# Main_PCB.net
KiCad netlist of a schematic drawn in EAGLE
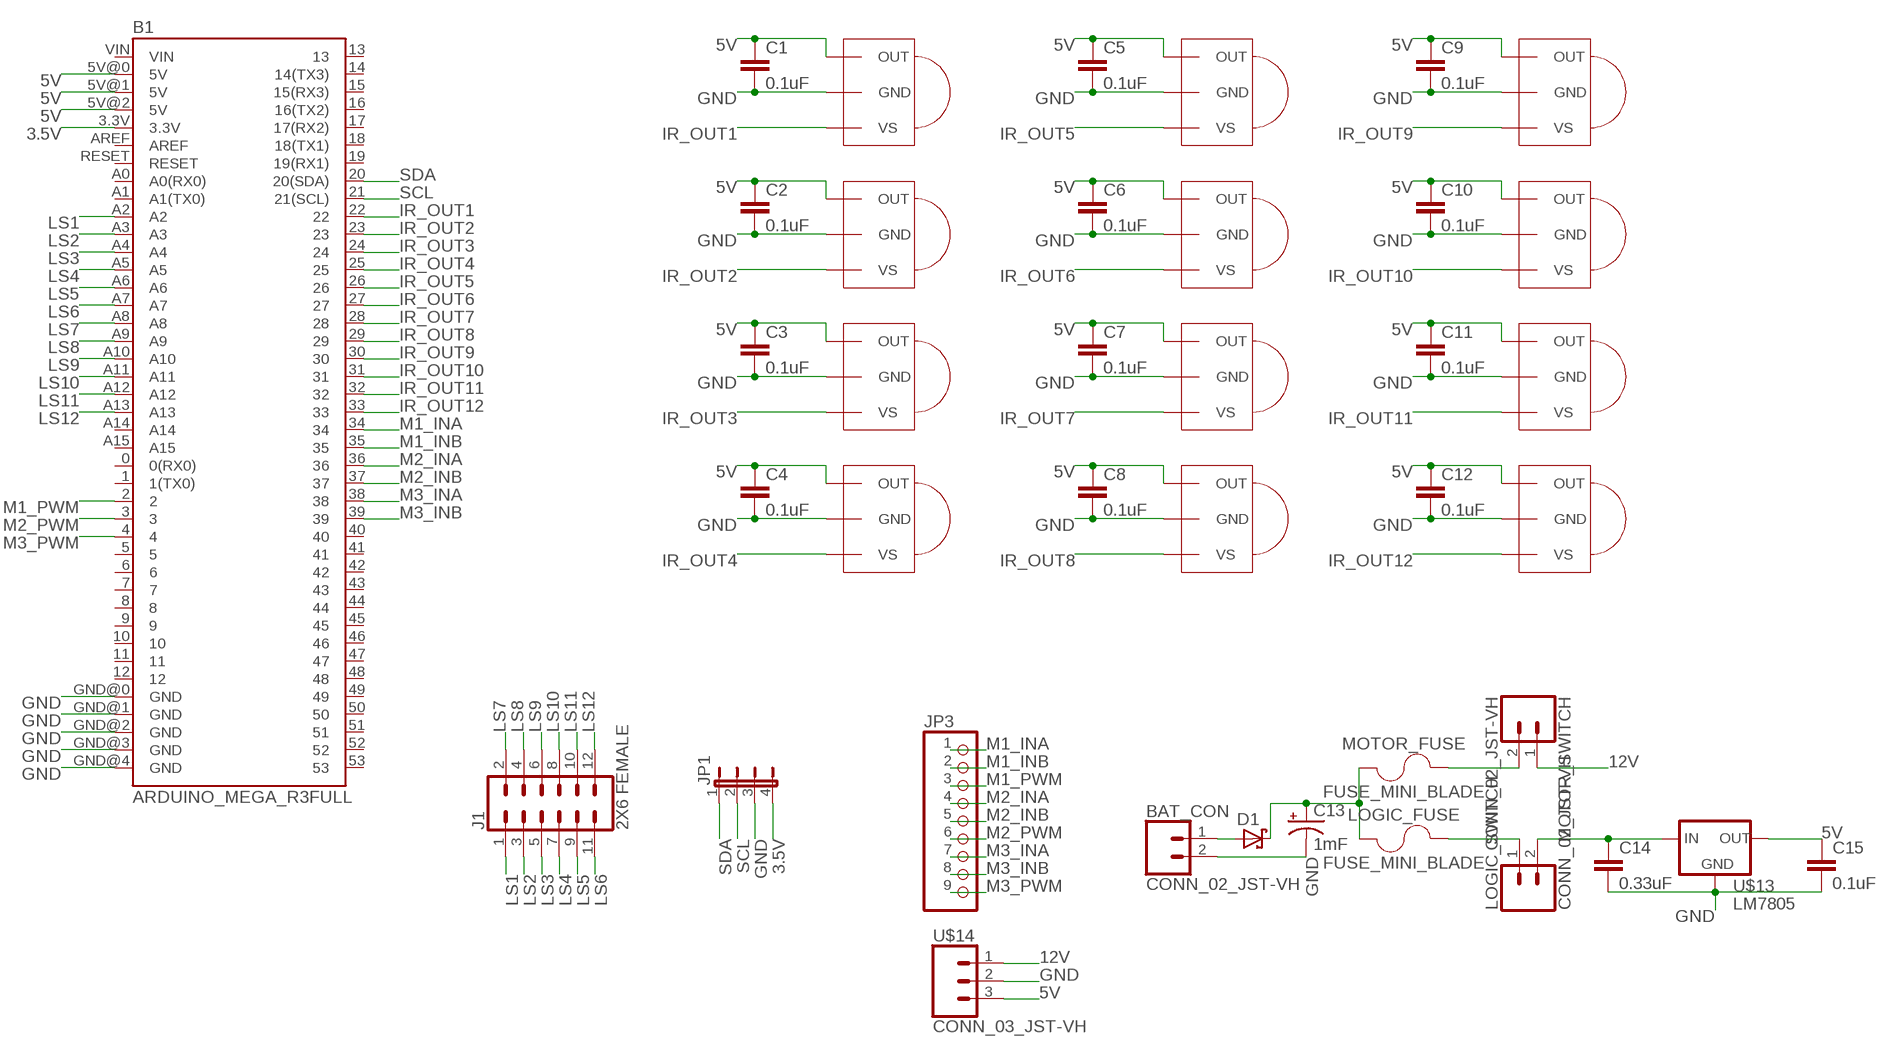
[diagram p0: schematic, sheet 1]

(export (version "E")
  (design (tool "Eeschema 10.0.6"))
  (components
    (comp (ref "B1")
      (value "ARDUINO_MEGA_R3FULL")
      (footprint "eagle-import:ARDUINO_MEGA")
      (libsource (lib "eagle-import") (part "ARDUINO_MEGA_R3FULL"))
    )
    (comp (ref "BAT_CON")
      (value "CONN_02_JST-VH")
      (footprint "eagle-import:B2P-VH")
      (libsource (lib "eagle-import") (part "CONN_02_JST-VH"))
    )
    (comp (ref "C1")
      (value "0.1uF")
      (footprint "eagle-import:0603")
      (libsource (lib "eagle-import") (part "0.1UF-0603-25V-(+80/-20%)"))
    )
    (comp (ref "C2")
      (value "0.1uF")
      (footprint "eagle-import:0603")
      (libsource (lib "eagle-import") (part "0.1UF-0603-25V-(+80/-20%)"))
    )
    (comp (ref "C3")
      (value "0.1uF")
      (footprint "eagle-import:0603")
      (libsource (lib "eagle-import") (part "0.1UF-0603-25V-(+80/-20%)"))
    )
    (comp (ref "C4")
      (value "0.1uF")
      (footprint "eagle-import:0603")
      (libsource (lib "eagle-import") (part "0.1UF-0603-25V-(+80/-20%)"))
    )
    (comp (ref "C5")
      (value "0.1uF")
      (footprint "eagle-import:0603")
      (libsource (lib "eagle-import") (part "0.1UF-0603-25V-(+80/-20%)"))
    )
    (comp (ref "C6")
      (value "0.1uF")
      (footprint "eagle-import:0603")
      (libsource (lib "eagle-import") (part "0.1UF-0603-25V-(+80/-20%)"))
    )
    (comp (ref "C7")
      (value "0.1uF")
      (footprint "eagle-import:0603")
      (libsource (lib "eagle-import") (part "0.1UF-0603-25V-(+80/-20%)"))
    )
    (comp (ref "C8")
      (value "0.1uF")
      (footprint "eagle-import:0603")
      (libsource (lib "eagle-import") (part "0.1UF-0603-25V-(+80/-20%)"))
    )
    (comp (ref "C9")
      (value "0.1uF")
      (footprint "eagle-import:0603")
      (libsource (lib "eagle-import") (part "0.1UF-0603-25V-(+80/-20%)"))
    )
    (comp (ref "C10")
      (value "0.1uF")
      (footprint "eagle-import:0603")
      (libsource (lib "eagle-import") (part "0.1UF-0603-25V-(+80/-20%)"))
    )
    (comp (ref "C11")
      (value "0.1uF")
      (footprint "eagle-import:0603")
      (libsource (lib "eagle-import") (part "0.1UF-0603-25V-(+80/-20%)"))
    )
    (comp (ref "C12")
      (value "0.1uF")
      (footprint "eagle-import:0603")
      (libsource (lib "eagle-import") (part "0.1UF-0603-25V-(+80/-20%)"))
    )
    (comp (ref "C13")
      (value "1mF")
      (footprint "eagle-import:CPOL-RADIAL-5MM-10MM")
      (libsource (lib "eagle-import") (part "1000UF-RADIAL-5MM-25V-20%"))
    )
    (comp (ref "C14")
      (value "0.33uF")
      (footprint "eagle-import:C5B3")
      (libsource (lib "eagle-import") (part "C5/3"))
    )
    (comp (ref "C15")
      (value "0.1uF")
      (footprint "eagle-import:C5B3")
      (libsource (lib "eagle-import") (part "C5/3"))
    )
    (comp (ref "D1")
      (value "SCHOTTKY-DIODEP6T15")
      (footprint "eagle-import:P6T15")
      (libsource (lib "eagle-import") (part "SCHOTTKY-DIODEP6T15"))
    )
    (comp (ref "J1")
      (value "2X6 FEMALE")
      (footprint "eagle-import:2X6")
      (libsource (lib "eagle-import") (part "CONN_06X2PTH_FEMALE"))
    )
    (comp (ref "JP1")
      (value "JP4E")
      (footprint "eagle-import:JP4")
      (libsource (lib "eagle-import") (part "JP4E"))
    )
    (comp (ref "JP3")
      (value "PINHD-1X9")
      (footprint "eagle-import:1X09")
      (libsource (lib "eagle-import") (part "PINHD-1X9"))
    )
    (comp (ref "LOGIC_FUSE")
      (value "FUSE_MINI_BLADE")
      (footprint "eagle-import:SL-1538")
      (libsource (lib "eagle-import") (part "FUSE_MINI_BLADE"))
    )
    (comp (ref "LOGIC_SWITCH")
      (value "CONN_02_JST-VH")
      (footprint "eagle-import:B2P-VH")
      (libsource (lib "eagle-import") (part "CONN_02_JST-VH"))
    )
    (comp (ref "MOTOR_FUSE")
      (value "FUSE_MINI_BLADE")
      (footprint "eagle-import:SL-1538")
      (libsource (lib "eagle-import") (part "FUSE_MINI_BLADE"))
    )
    (comp (ref "MOTOR_SWITCH")
      (value "CONN_02_JST-VH")
      (footprint "eagle-import:B2P-VH")
      (libsource (lib "eagle-import") (part "CONN_02_JST-VH"))
    )
    (comp (ref "U$1")
      (value "TSSP58038")
      (footprint "eagle-import:MINICAST")
      (libsource (lib "eagle-import") (part "TSSP58038"))
    )
    (comp (ref "U$2")
      (value "TSSP58038")
      (footprint "eagle-import:MINICAST")
      (libsource (lib "eagle-import") (part "TSSP58038"))
    )
    (comp (ref "U$3")
      (value "TSSP58038")
      (footprint "eagle-import:MINICAST")
      (libsource (lib "eagle-import") (part "TSSP58038"))
    )
    (comp (ref "U$4")
      (value "TSSP58038")
      (footprint "eagle-import:MINICAST")
      (libsource (lib "eagle-import") (part "TSSP58038"))
    )
    (comp (ref "U$5")
      (value "TSSP58038")
      (footprint "eagle-import:MINICAST")
      (libsource (lib "eagle-import") (part "TSSP58038"))
    )
    (comp (ref "U$6")
      (value "TSSP58038")
      (footprint "eagle-import:MINICAST")
      (libsource (lib "eagle-import") (part "TSSP58038"))
    )
    (comp (ref "U$7")
      (value "TSSP58038")
      (footprint "eagle-import:MINICAST")
      (libsource (lib "eagle-import") (part "TSSP58038"))
    )
    (comp (ref "U$8")
      (value "TSSP58038")
      (footprint "eagle-import:MINICAST")
      (libsource (lib "eagle-import") (part "TSSP58038"))
    )
    (comp (ref "U$9")
      (value "TSSP58038")
      (footprint "eagle-import:MINICAST")
      (libsource (lib "eagle-import") (part "TSSP58038"))
    )
    (comp (ref "U$10")
      (value "TSSP58038")
      (footprint "eagle-import:MINICAST")
      (libsource (lib "eagle-import") (part "TSSP58038"))
    )
    (comp (ref "U$11")
      (value "TSSP58038")
      (footprint "eagle-import:MINICAST")
      (libsource (lib "eagle-import") (part "TSSP58038"))
    )
    (comp (ref "U$12")
      (value "TSSP58038")
      (footprint "eagle-import:MINICAST")
      (libsource (lib "eagle-import") (part "TSSP58038"))
    )
    (comp (ref "U$13")
      (value "LM7805")
      (footprint "eagle-import:TO220-ADJ")
      (libsource (lib "eagle-import") (part "LM7805"))
    )
    (comp (ref "U$14")
      (value "CONN_03_JST-VH")
      (footprint "eagle-import:B3P-VH")
      (libsource (lib "eagle-import") (part "CONN_03_JST-VH"))
    )
  )
  (nets
    (net (code "1") (name "/3.5V") (class "Default")
      (node (ref "B1") (pin "3.3V") (pinfunction "3.3V_3.3V") (pintype "bidirectional"))
      (node (ref "JP1") (pin "4") (pinfunction "4_4") (pintype "passive"))
    )
    (net (code "2") (name "/5V") (class "Default")
      (node (ref "B1") (pin "5V@0") (pinfunction "5V_5V@0") (pintype "bidirectional"))
      (node (ref "B1") (pin "5V@1") (pinfunction "5V_5V@1") (pintype "bidirectional"))
      (node (ref "B1") (pin "5V@2") (pinfunction "5V_5V@2") (pintype "bidirectional"))
      (node (ref "C1") (pin "1") (pinfunction "1_1") (pintype "passive"))
      (node (ref "C10") (pin "1") (pinfunction "1_1") (pintype "passive"))
      (node (ref "C11") (pin "1") (pinfunction "1_1") (pintype "passive"))
      (node (ref "C12") (pin "1") (pinfunction "1_1") (pintype "passive"))
      (node (ref "C15") (pin "1") (pinfunction "1_1") (pintype "passive"))
      (node (ref "C2") (pin "1") (pinfunction "1_1") (pintype "passive"))
      (node (ref "C3") (pin "1") (pinfunction "1_1") (pintype "passive"))
      (node (ref "C4") (pin "1") (pinfunction "1_1") (pintype "passive"))
      (node (ref "C5") (pin "1") (pinfunction "1_1") (pintype "passive"))
      (node (ref "C6") (pin "1") (pinfunction "1_1") (pintype "passive"))
      (node (ref "C7") (pin "1") (pinfunction "1_1") (pintype "passive"))
      (node (ref "C8") (pin "1") (pinfunction "1_1") (pintype "passive"))
      (node (ref "C9") (pin "1") (pinfunction "1_1") (pintype "passive"))
      (node (ref "U$1") (pin "1") (pinfunction "OUT_1") (pintype "bidirectional"))
      (node (ref "U$10") (pin "1") (pinfunction "OUT_1") (pintype "bidirectional"))
      (node (ref "U$11") (pin "1") (pinfunction "OUT_1") (pintype "bidirectional"))
      (node (ref "U$12") (pin "1") (pinfunction "OUT_1") (pintype "bidirectional"))
      (node (ref "U$13") (pin "OUTPUT") (pinfunction "OUT_OUTPUT") (pintype "passive"))
      (node (ref "U$14") (pin "3") (pinfunction "3_3") (pintype "passive"))
      (node (ref "U$2") (pin "1") (pinfunction "OUT_1") (pintype "bidirectional"))
      (node (ref "U$3") (pin "1") (pinfunction "OUT_1") (pintype "bidirectional"))
      (node (ref "U$4") (pin "1") (pinfunction "OUT_1") (pintype "bidirectional"))
      (node (ref "U$5") (pin "1") (pinfunction "OUT_1") (pintype "bidirectional"))
      (node (ref "U$6") (pin "1") (pinfunction "OUT_1") (pintype "bidirectional"))
      (node (ref "U$7") (pin "1") (pinfunction "OUT_1") (pintype "bidirectional"))
      (node (ref "U$8") (pin "1") (pinfunction "OUT_1") (pintype "bidirectional"))
      (node (ref "U$9") (pin "1") (pinfunction "OUT_1") (pintype "bidirectional"))
    )
    (net (code "3") (name "/12V") (class "Default")
      (node (ref "MOTOR_SWITCH") (pin "1") (pinfunction "1_1") (pintype "passive"))
      (node (ref "U$14") (pin "1") (pinfunction "1_1") (pintype "passive"))
    )
    (net (code "4") (name "/GND") (class "Default")
      (node (ref "B1") (pin "GND@0") (pinfunction "GND_GND@0") (pintype "bidirectional"))
      (node (ref "B1") (pin "GND@1") (pinfunction "GND_GND@1") (pintype "bidirectional"))
      (node (ref "B1") (pin "GND@2") (pinfunction "GND_GND@2") (pintype "bidirectional"))
      (node (ref "B1") (pin "GND@3") (pinfunction "GND_GND@3") (pintype "bidirectional"))
      (node (ref "B1") (pin "GND@4") (pinfunction "GND_GND@4") (pintype "bidirectional"))
      (node (ref "BAT_CON") (pin "2") (pinfunction "2_2") (pintype "passive"))
      (node (ref "C1") (pin "2") (pinfunction "2_2") (pintype "passive"))
      (node (ref "C10") (pin "2") (pinfunction "2_2") (pintype "passive"))
      (node (ref "C11") (pin "2") (pinfunction "2_2") (pintype "passive"))
      (node (ref "C12") (pin "2") (pinfunction "2_2") (pintype "passive"))
      (node (ref "C13") (pin "-") (pinfunction "-_-") (pintype "passive"))
      (node (ref "C14") (pin "2") (pinfunction "2_2") (pintype "passive"))
      (node (ref "C15") (pin "2") (pinfunction "2_2") (pintype "passive"))
      (node (ref "C2") (pin "2") (pinfunction "2_2") (pintype "passive"))
      (node (ref "C3") (pin "2") (pinfunction "2_2") (pintype "passive"))
      (node (ref "C4") (pin "2") (pinfunction "2_2") (pintype "passive"))
      (node (ref "C5") (pin "2") (pinfunction "2_2") (pintype "passive"))
      (node (ref "C6") (pin "2") (pinfunction "2_2") (pintype "passive"))
      (node (ref "C7") (pin "2") (pinfunction "2_2") (pintype "passive"))
      (node (ref "C8") (pin "2") (pinfunction "2_2") (pintype "passive"))
      (node (ref "C9") (pin "2") (pinfunction "2_2") (pintype "passive"))
      (node (ref "JP1") (pin "3") (pinfunction "3_3") (pintype "passive"))
      (node (ref "U$1") (pin "2") (pinfunction "GND_2") (pintype "bidirectional"))
      (node (ref "U$10") (pin "2") (pinfunction "GND_2") (pintype "bidirectional"))
      (node (ref "U$11") (pin "2") (pinfunction "GND_2") (pintype "bidirectional"))
      (node (ref "U$12") (pin "2") (pinfunction "GND_2") (pintype "bidirectional"))
      (node (ref "U$13") (pin "GND") (pinfunction "GND_GND") (pintype "input"))
      (node (ref "U$14") (pin "2") (pinfunction "2_2") (pintype "passive"))
      (node (ref "U$2") (pin "2") (pinfunction "GND_2") (pintype "bidirectional"))
      (node (ref "U$3") (pin "2") (pinfunction "GND_2") (pintype "bidirectional"))
      (node (ref "U$4") (pin "2") (pinfunction "GND_2") (pintype "bidirectional"))
      (node (ref "U$5") (pin "2") (pinfunction "GND_2") (pintype "bidirectional"))
      (node (ref "U$6") (pin "2") (pinfunction "GND_2") (pintype "bidirectional"))
      (node (ref "U$7") (pin "2") (pinfunction "GND_2") (pintype "bidirectional"))
      (node (ref "U$8") (pin "2") (pinfunction "GND_2") (pintype "bidirectional"))
      (node (ref "U$9") (pin "2") (pinfunction "GND_2") (pintype "bidirectional"))
    )
    (net (code "5") (name "/IR_OUT1") (class "Default")
      (node (ref "B1") (pin "22") (pinfunction "22_22") (pintype "bidirectional"))
      (node (ref "U$1") (pin "3") (pinfunction "VS_3") (pintype "bidirectional"))
    )
    (net (code "6") (name "/IR_OUT2") (class "Default")
      (node (ref "B1") (pin "23") (pinfunction "23_23") (pintype "bidirectional"))
      (node (ref "U$2") (pin "3") (pinfunction "VS_3") (pintype "bidirectional"))
    )
    (net (code "7") (name "/IR_OUT3") (class "Default")
      (node (ref "B1") (pin "24") (pinfunction "24_24") (pintype "bidirectional"))
      (node (ref "U$3") (pin "3") (pinfunction "VS_3") (pintype "bidirectional"))
    )
    (net (code "8") (name "/IR_OUT4") (class "Default")
      (node (ref "B1") (pin "25") (pinfunction "25_25") (pintype "bidirectional"))
      (node (ref "U$4") (pin "3") (pinfunction "VS_3") (pintype "bidirectional"))
    )
    (net (code "9") (name "/IR_OUT5") (class "Default")
      (node (ref "B1") (pin "26") (pinfunction "26_26") (pintype "bidirectional"))
      (node (ref "U$5") (pin "3") (pinfunction "VS_3") (pintype "bidirectional"))
    )
    (net (code "10") (name "/IR_OUT6") (class "Default")
      (node (ref "B1") (pin "27") (pinfunction "27_27") (pintype "bidirectional"))
      (node (ref "U$6") (pin "3") (pinfunction "VS_3") (pintype "bidirectional"))
    )
    (net (code "11") (name "/IR_OUT7") (class "Default")
      (node (ref "B1") (pin "28") (pinfunction "28_28") (pintype "bidirectional"))
      (node (ref "U$7") (pin "3") (pinfunction "VS_3") (pintype "bidirectional"))
    )
    (net (code "12") (name "/IR_OUT8") (class "Default")
      (node (ref "B1") (pin "29") (pinfunction "29_29") (pintype "bidirectional"))
      (node (ref "U$8") (pin "3") (pinfunction "VS_3") (pintype "bidirectional"))
    )
    (net (code "13") (name "/IR_OUT9") (class "Default")
      (node (ref "B1") (pin "30") (pinfunction "30_30") (pintype "bidirectional"))
      (node (ref "U$9") (pin "3") (pinfunction "VS_3") (pintype "bidirectional"))
    )
    (net (code "14") (name "/IR_OUT10") (class "Default")
      (node (ref "B1") (pin "31") (pinfunction "31_31") (pintype "bidirectional"))
      (node (ref "U$10") (pin "3") (pinfunction "VS_3") (pintype "bidirectional"))
    )
    (net (code "15") (name "/IR_OUT11") (class "Default")
      (node (ref "B1") (pin "32") (pinfunction "32_32") (pintype "bidirectional"))
      (node (ref "U$11") (pin "3") (pinfunction "VS_3") (pintype "bidirectional"))
    )
    (net (code "16") (name "/IR_OUT12") (class "Default")
      (node (ref "B1") (pin "33") (pinfunction "33_33") (pintype "bidirectional"))
      (node (ref "U$12") (pin "3") (pinfunction "VS_3") (pintype "bidirectional"))
    )
    (net (code "17") (name "/LS1") (class "Default")
      (node (ref "B1") (pin "A2") (pinfunction "A2_A2") (pintype "bidirectional"))
      (node (ref "J1") (pin "1") (pinfunction "1_1") (pintype "passive"))
    )
    (net (code "18") (name "/LS2") (class "Default")
      (node (ref "B1") (pin "A3") (pinfunction "A3_A3") (pintype "bidirectional"))
      (node (ref "J1") (pin "3") (pinfunction "3_3") (pintype "passive"))
    )
    (net (code "19") (name "/LS3") (class "Default")
      (node (ref "B1") (pin "A4") (pinfunction "A4_A4") (pintype "bidirectional"))
      (node (ref "J1") (pin "5") (pinfunction "5_5") (pintype "passive"))
    )
    (net (code "20") (name "/LS4") (class "Default")
      (node (ref "B1") (pin "A5") (pinfunction "A5_A5") (pintype "bidirectional"))
      (node (ref "J1") (pin "7") (pinfunction "7_7") (pintype "passive"))
    )
    (net (code "21") (name "/LS5") (class "Default")
      (node (ref "B1") (pin "A6") (pinfunction "A6_A6") (pintype "bidirectional"))
      (node (ref "J1") (pin "9") (pinfunction "9_9") (pintype "passive"))
    )
    (net (code "22") (name "/LS6") (class "Default")
      (node (ref "B1") (pin "A7") (pinfunction "A7_A7") (pintype "bidirectional"))
      (node (ref "J1") (pin "11") (pinfunction "11_11") (pintype "passive"))
    )
    (net (code "23") (name "/LS7") (class "Default")
      (node (ref "B1") (pin "A8") (pinfunction "A8_A8") (pintype "bidirectional"))
      (node (ref "J1") (pin "2") (pinfunction "2_2") (pintype "passive"))
    )
    (net (code "24") (name "/LS8") (class "Default")
      (node (ref "B1") (pin "A9") (pinfunction "A9_A9") (pintype "bidirectional"))
      (node (ref "J1") (pin "4") (pinfunction "4_4") (pintype "passive"))
    )
    (net (code "25") (name "/LS9") (class "Default")
      (node (ref "B1") (pin "A10") (pinfunction "A10_A10") (pintype "bidirectional"))
      (node (ref "J1") (pin "6") (pinfunction "6_6") (pintype "passive"))
    )
    (net (code "26") (name "/LS10") (class "Default")
      (node (ref "B1") (pin "A11") (pinfunction "A11_A11") (pintype "bidirectional"))
      (node (ref "J1") (pin "8") (pinfunction "8_8") (pintype "passive"))
    )
    (net (code "27") (name "/LS11") (class "Default")
      (node (ref "B1") (pin "A12") (pinfunction "A12_A12") (pintype "bidirectional"))
      (node (ref "J1") (pin "10") (pinfunction "10_10") (pintype "passive"))
    )
    (net (code "28") (name "/LS12") (class "Default")
      (node (ref "B1") (pin "A13") (pinfunction "A13_A13") (pintype "bidirectional"))
      (node (ref "J1") (pin "12") (pinfunction "12_12") (pintype "passive"))
    )
    (net (code "29") (name "/M1_INA") (class "Default")
      (node (ref "B1") (pin "34") (pinfunction "34_34") (pintype "bidirectional"))
      (node (ref "JP3") (pin "1") (pinfunction "1_1") (pintype "passive"))
    )
    (net (code "30") (name "/M1_INB") (class "Default")
      (node (ref "B1") (pin "35") (pinfunction "35_35") (pintype "bidirectional"))
      (node (ref "JP3") (pin "2") (pinfunction "2_2") (pintype "passive"))
    )
    (net (code "31") (name "/M1_PWM") (class "Default")
      (node (ref "B1") (pin "2") (pinfunction "2_2") (pintype "bidirectional"))
      (node (ref "JP3") (pin "3") (pinfunction "3_3") (pintype "passive"))
    )
    (net (code "32") (name "/M2_INA") (class "Default")
      (node (ref "B1") (pin "36") (pinfunction "36_36") (pintype "bidirectional"))
      (node (ref "JP3") (pin "4") (pinfunction "4_4") (pintype "passive"))
    )
    (net (code "33") (name "/M2_INB") (class "Default")
      (node (ref "B1") (pin "37") (pinfunction "37_37") (pintype "bidirectional"))
      (node (ref "JP3") (pin "5") (pinfunction "5_5") (pintype "passive"))
    )
    (net (code "34") (name "/M2_PWM") (class "Default")
      (node (ref "B1") (pin "3") (pinfunction "3_3") (pintype "bidirectional"))
      (node (ref "JP3") (pin "6") (pinfunction "6_6") (pintype "passive"))
    )
    (net (code "35") (name "/M3_INA") (class "Default")
      (node (ref "B1") (pin "38") (pinfunction "38_38") (pintype "bidirectional"))
      (node (ref "JP3") (pin "7") (pinfunction "7_7") (pintype "passive"))
    )
    (net (code "36") (name "/M3_INB") (class "Default")
      (node (ref "B1") (pin "39") (pinfunction "39_39") (pintype "bidirectional"))
      (node (ref "JP3") (pin "8") (pinfunction "8_8") (pintype "passive"))
    )
    (net (code "37") (name "/M3_PWM") (class "Default")
      (node (ref "B1") (pin "4") (pinfunction "4_4") (pintype "bidirectional"))
      (node (ref "JP3") (pin "9") (pinfunction "9_9") (pintype "passive"))
    )
    (net (code "38") (name "/SCL") (class "Default")
      (node (ref "B1") (pin "21") (pinfunction "21(SCL)_21") (pintype "bidirectional"))
      (node (ref "JP1") (pin "2") (pinfunction "2_2") (pintype "passive"))
    )
    (net (code "39") (name "/SDA") (class "Default")
      (node (ref "B1") (pin "20") (pinfunction "20(SDA)_20") (pintype "bidirectional"))
      (node (ref "JP1") (pin "1") (pinfunction "1_1") (pintype "passive"))
    )
    (net (code "40") (name "Net-(BAT_CON-Pad1)") (class "Default")
      (node (ref "BAT_CON") (pin "1") (pinfunction "1_1") (pintype "passive"))
      (node (ref "D1") (pin "A") (pinfunction "A_A") (pintype "passive"))
    )
    (net (code "41") (name "Net-(LOGIC_FUSE-1)") (class "Default")
      (node (ref "C13") (pin "+") (pinfunction "+_+") (pintype "passive"))
      (node (ref "D1") (pin "C") (pinfunction "C_C") (pintype "passive"))
      (node (ref "LOGIC_FUSE") (pin "P$1") (pinfunction "1_P$1") (pintype "bidirectional"))
      (node (ref "MOTOR_FUSE") (pin "P$1") (pinfunction "1_P$1") (pintype "bidirectional"))
    )
    (net (code "42") (name "Net-(LOGIC_FUSE-2)") (class "Default")
      (node (ref "LOGIC_FUSE") (pin "P$2") (pinfunction "2_P$2") (pintype "bidirectional"))
      (node (ref "LOGIC_SWITCH") (pin "1") (pinfunction "1_1") (pintype "passive"))
    )
    (net (code "43") (name "Net-(MOTOR_FUSE-2)") (class "Default")
      (node (ref "MOTOR_FUSE") (pin "P$2") (pinfunction "2_P$2") (pintype "bidirectional"))
      (node (ref "MOTOR_SWITCH") (pin "2") (pinfunction "2_2") (pintype "passive"))
    )
    (net (code "44") (name "Net-(U$13-IN)") (class "Default")
      (node (ref "C14") (pin "1") (pinfunction "1_1") (pintype "passive"))
      (node (ref "LOGIC_SWITCH") (pin "2") (pinfunction "2_2") (pintype "passive"))
      (node (ref "U$13") (pin "INPUT") (pinfunction "IN_INPUT") (pintype "input"))
    )
    (net (code "45") (name "unconnected-(B1-0(RX0)-Pad0)") (class "Default")
      (node (ref "B1") (pin "0") (pinfunction "0(RX0)_0") (pintype "bidirectional"))
    )
    (net (code "46") (name "unconnected-(B1-1(TX0)-Pad1)") (class "Default")
      (node (ref "B1") (pin "1") (pinfunction "1(TX0)_1") (pintype "bidirectional"))
    )
    (net (code "47") (name "unconnected-(B1-14(TX3)-Pad14)") (class "Default")
      (node (ref "B1") (pin "14") (pinfunction "14(TX3)_14") (pintype "bidirectional"))
    )
    (net (code "48") (name "unconnected-(B1-15(RX3)-Pad15)") (class "Default")
      (node (ref "B1") (pin "15") (pinfunction "15(RX3)_15") (pintype "bidirectional"))
    )
    (net (code "49") (name "unconnected-(B1-16(TX2)-Pad16)") (class "Default")
      (node (ref "B1") (pin "16") (pinfunction "16(TX2)_16") (pintype "bidirectional"))
    )
    (net (code "50") (name "unconnected-(B1-17(RX2)-Pad17)") (class "Default")
      (node (ref "B1") (pin "17") (pinfunction "17(RX2)_17") (pintype "bidirectional"))
    )
    (net (code "51") (name "unconnected-(B1-18(TX1)-Pad18)") (class "Default")
      (node (ref "B1") (pin "18") (pinfunction "18(TX1)_18") (pintype "bidirectional"))
    )
    (net (code "52") (name "unconnected-(B1-19(RX1)-Pad19)") (class "Default")
      (node (ref "B1") (pin "19") (pinfunction "19(RX1)_19") (pintype "bidirectional"))
    )
    (net (code "53") (name "unconnected-(B1-A0(RX0)-PadA0)") (class "Default")
      (node (ref "B1") (pin "A0") (pinfunction "A0(RX0)_A0") (pintype "bidirectional"))
    )
    (net (code "54") (name "unconnected-(B1-A1(TX0)-PadA1)") (class "Default")
      (node (ref "B1") (pin "A1") (pinfunction "A1(TX0)_A1") (pintype "bidirectional"))
    )
    (net (code "55") (name "unconnected-(B1-Pad5)") (class "Default")
      (node (ref "B1") (pin "5") (pinfunction "5_5") (pintype "bidirectional"))
    )
    (net (code "56") (name "unconnected-(B1-Pad6)") (class "Default")
      (node (ref "B1") (pin "6") (pinfunction "6_6") (pintype "bidirectional"))
    )
    (net (code "57") (name "unconnected-(B1-Pad7)") (class "Default")
      (node (ref "B1") (pin "7") (pinfunction "7_7") (pintype "bidirectional"))
    )
    (net (code "58") (name "unconnected-(B1-Pad8)") (class "Default")
      (node (ref "B1") (pin "8") (pinfunction "8_8") (pintype "bidirectional"))
    )
    (net (code "59") (name "unconnected-(B1-Pad9)") (class "Default")
      (node (ref "B1") (pin "9") (pinfunction "9_9") (pintype "bidirectional"))
    )
    (net (code "60") (name "unconnected-(B1-Pad10)") (class "Default")
      (node (ref "B1") (pin "10") (pinfunction "10_10") (pintype "bidirectional"))
    )
    (net (code "61") (name "unconnected-(B1-Pad11)") (class "Default")
      (node (ref "B1") (pin "11") (pinfunction "11_11") (pintype "bidirectional"))
    )
    (net (code "62") (name "unconnected-(B1-Pad12)") (class "Default")
      (node (ref "B1") (pin "12") (pinfunction "12_12") (pintype "bidirectional"))
    )
    (net (code "63") (name "unconnected-(B1-Pad13)") (class "Default")
      (node (ref "B1") (pin "13") (pinfunction "13_13") (pintype "bidirectional"))
    )
    (net (code "64") (name "unconnected-(B1-Pad40)") (class "Default")
      (node (ref "B1") (pin "40") (pinfunction "40_40") (pintype "bidirectional"))
    )
    (net (code "65") (name "unconnected-(B1-Pad41)") (class "Default")
      (node (ref "B1") (pin "41") (pinfunction "41_41") (pintype "bidirectional"))
    )
    (net (code "66") (name "unconnected-(B1-Pad42)") (class "Default")
      (node (ref "B1") (pin "42") (pinfunction "42_42") (pintype "bidirectional"))
    )
    (net (code "67") (name "unconnected-(B1-Pad43)") (class "Default")
      (node (ref "B1") (pin "43") (pinfunction "43_43") (pintype "bidirectional"))
    )
    (net (code "68") (name "unconnected-(B1-Pad44)") (class "Default")
      (node (ref "B1") (pin "44") (pinfunction "44_44") (pintype "bidirectional"))
    )
    (net (code "69") (name "unconnected-(B1-Pad45)") (class "Default")
      (node (ref "B1") (pin "45") (pinfunction "45_45") (pintype "bidirectional"))
    )
    (net (code "70") (name "unconnected-(B1-Pad46)") (class "Default")
      (node (ref "B1") (pin "46") (pinfunction "46_46") (pintype "bidirectional"))
    )
    (net (code "71") (name "unconnected-(B1-Pad47)") (class "Default")
      (node (ref "B1") (pin "47") (pinfunction "47_47") (pintype "bidirectional"))
    )
    (net (code "72") (name "unconnected-(B1-Pad48)") (class "Default")
      (node (ref "B1") (pin "48") (pinfunction "48_48") (pintype "bidirectional"))
    )
    (net (code "73") (name "unconnected-(B1-Pad49)") (class "Default")
      (node (ref "B1") (pin "49") (pinfunction "49_49") (pintype "bidirectional"))
    )
    (net (code "74") (name "unconnected-(B1-Pad50)") (class "Default")
      (node (ref "B1") (pin "50") (pinfunction "50_50") (pintype "bidirectional"))
    )
    (net (code "75") (name "unconnected-(B1-Pad51)") (class "Default")
      (node (ref "B1") (pin "51") (pinfunction "51_51") (pintype "bidirectional"))
    )
    (net (code "76") (name "unconnected-(B1-Pad52)") (class "Default")
      (node (ref "B1") (pin "52") (pinfunction "52_52") (pintype "bidirectional"))
    )
    (net (code "77") (name "unconnected-(B1-Pad53)") (class "Default")
      (node (ref "B1") (pin "53") (pinfunction "53_53") (pintype "bidirectional"))
    )
    (net (code "78") (name "unconnected-(B1-PadA14)") (class "Default")
      (node (ref "B1") (pin "A14") (pinfunction "A14_A14") (pintype "bidirectional"))
    )
    (net (code "79") (name "unconnected-(B1-PadA15)") (class "Default")
      (node (ref "B1") (pin "A15") (pinfunction "A15_A15") (pintype "bidirectional"))
    )
    (net (code "80") (name "unconnected-(B1-PadAREF)") (class "Default")
      (node (ref "B1") (pin "AREF") (pinfunction "AREF_AREF") (pintype "bidirectional"))
    )
    (net (code "81") (name "unconnected-(B1-PadRESET)") (class "Default")
      (node (ref "B1") (pin "RESET") (pinfunction "RESET_RESET") (pintype "bidirectional"))
    )
    (net (code "82") (name "unconnected-(B1-PadVIN)") (class "Default")
      (node (ref "B1") (pin "VIN") (pinfunction "VIN_VIN") (pintype "bidirectional"))
    )
  )
)
